# Sheet2.net
KiCad netlist of a schematic drawn in Altium Designer
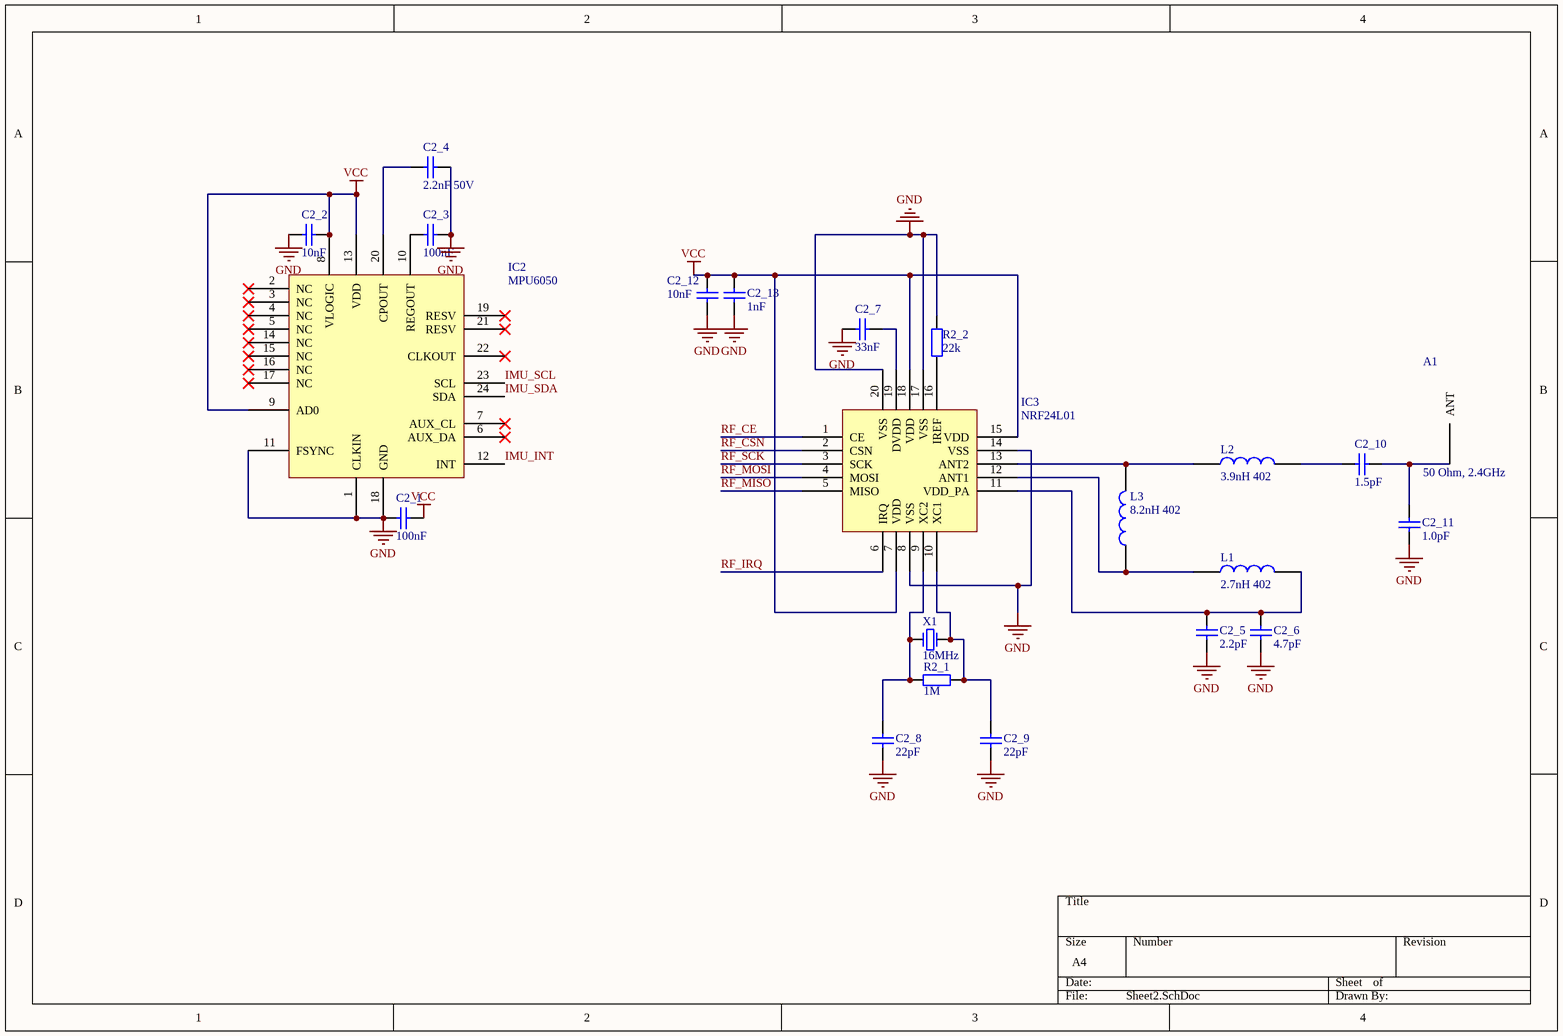
[diagram p0: Sheet2.SchDoc]

(export (version "E")
  (design (tool "Eeschema 10.0.6"))
  (components
    (comp (ref "A1")
      (value "50 Ohm, 2.4GHz")
      (footprint "Antene")
      (libsource (lib "Integrated_Library1") (part "Antenne"))
    )
    (comp (ref "C2_1")
      (value "100nF")
      (footprint "cms805")
      (libsource (lib "Integrated_Library1") (part "Capa"))
    )
    (comp (ref "C2_2")
      (value "10nF")
      (footprint "cms805")
      (libsource (lib "Integrated_Library1") (part "Capa"))
    )
    (comp (ref "C2_3")
      (value "100nF")
      (footprint "cms805")
      (libsource (lib "Integrated_Library1") (part "Capa"))
    )
    (comp (ref "C2_4")
      (value "2.2nF 50V")
      (footprint "cms805")
      (libsource (lib "Integrated_Library1") (part "Capa"))
    )
    (comp (ref "C2_5")
      (value "2.2pF")
      (footprint "cms805")
      (libsource (lib "Integrated_Library1") (part "Capa"))
    )
    (comp (ref "C2_6")
      (value "4.7pF")
      (footprint "cms805")
      (libsource (lib "Integrated_Library1") (part "Capa"))
    )
    (comp (ref "C2_7")
      (value "33nF")
      (footprint "cms805")
      (libsource (lib "Integrated_Library1") (part "Capa"))
    )
    (comp (ref "C2_8")
      (value "22pF")
      (footprint "cms805")
      (libsource (lib "Integrated_Library1") (part "Capa"))
    )
    (comp (ref "C2_9")
      (value "22pF")
      (footprint "cms805")
      (libsource (lib "Integrated_Library1") (part "Capa"))
    )
    (comp (ref "C2_10")
      (value "1.5pF")
      (footprint "cms805")
      (libsource (lib "Integrated_Library1") (part "Capa"))
    )
    (comp (ref "C2_11")
      (value "1.0pF")
      (footprint "cms805")
      (libsource (lib "Integrated_Library1") (part "Capa"))
    )
    (comp (ref "C2_12")
      (value "10nF")
      (footprint "cms805")
      (libsource (lib "Integrated_Library1") (part "Capa"))
    )
    (comp (ref "C2_13")
      (value "1nF")
      (footprint "cms805")
      (libsource (lib "Integrated_Library1") (part "Capa"))
    )
    (comp (ref "IC2")
      (value "MPU6050")
      (footprint "24QFN")
      (libsource (lib "Integrated_Library1") (part "MPU6050"))
    )
    (comp (ref "IC3")
      (value "NRF24L01")
      (footprint "20QFN")
      (libsource (lib "Integrated_Library1") (part "NRF24L01"))
    )
    (comp (ref "L1")
      (value "2.7nH 402")
      (footprint "CMS402")
      (libsource (lib "Integrated_Library1") (part "Inductance"))
    )
    (comp (ref "L2")
      (value "3.9nH 402")
      (footprint "CMS402")
      (libsource (lib "Integrated_Library1") (part "Inductance"))
    )
    (comp (ref "L3")
      (value "8.2nH 402")
      (footprint "CMS402")
      (libsource (lib "Integrated_Library1") (part "Inductance"))
    )
    (comp (ref "R2_1") (value "1M") (footprint "cms805") (libsource (lib "") (part "Resistance_1")))
    (comp (ref "R2_2")
      (value "22k")
      (footprint "cms805")
      (libsource (lib "Integrated_Library1") (part "Resistance"))
    )
    (comp (ref "X1")
      (value "16MHz")
      (footprint "Quartz")
      (libsource (lib "Integrated_Library1") (part "Quartz"))
    )
  )
  (nets
    (net (code "1") (name "/IMU_INT") (class "Default")
      (node (ref "IC2") (pin "12") (pinfunction "INT_12") (pintype "passive"))
    )
    (net (code "2") (name "/IMU_SCL") (class "Default")
      (node (ref "IC2") (pin "23") (pinfunction "SCL_23") (pintype "passive"))
    )
    (net (code "3") (name "/IMU_SDA") (class "Default")
      (node (ref "IC2") (pin "24") (pinfunction "SDA_24") (pintype "passive"))
    )
    (net (code "4") (name "/RF_CE") (class "Default")
      (node (ref "IC3") (pin "1") (pinfunction "CE_1") (pintype "passive"))
    )
    (net (code "5") (name "/RF_CSN") (class "Default")
      (node (ref "IC3") (pin "2") (pinfunction "CSN_2") (pintype "passive"))
    )
    (net (code "6") (name "/RF_IRQ") (class "Default")
      (node (ref "IC3") (pin "6") (pinfunction "IRQ_6") (pintype "passive"))
    )
    (net (code "7") (name "/RF_MISO") (class "Default")
      (node (ref "IC3") (pin "5") (pinfunction "MISO_5") (pintype "passive"))
    )
    (net (code "8") (name "/RF_MOSI") (class "Default")
      (node (ref "IC3") (pin "4") (pinfunction "MOSI_4") (pintype "passive"))
    )
    (net (code "9") (name "/RF_SCK") (class "Default")
      (node (ref "IC3") (pin "3") (pinfunction "SCK_3") (pintype "passive"))
    )
    (net (code "10") (name "GND") (class "Default")
      (node (ref "C2_1") (pin "1") (pinfunction "1_1") (pintype "passive"))
      (node (ref "C2_11") (pin "2") (pinfunction "2_2") (pintype "passive"))
      (node (ref "C2_12") (pin "2") (pinfunction "2_2") (pintype "passive"))
      (node (ref "C2_13") (pin "2") (pinfunction "2_2") (pintype "passive"))
      (node (ref "C2_2") (pin "2") (pinfunction "2_2") (pintype "passive"))
      (node (ref "C2_3") (pin "2") (pinfunction "2_2") (pintype "passive"))
      (node (ref "C2_4") (pin "1") (pinfunction "1_1") (pintype "passive"))
      (node (ref "C2_5") (pin "2") (pinfunction "2_2") (pintype "passive"))
      (node (ref "C2_6") (pin "2") (pinfunction "2_2") (pintype "passive"))
      (node (ref "C2_7") (pin "2") (pinfunction "2_2") (pintype "passive"))
      (node (ref "C2_8") (pin "1") (pinfunction "1_1") (pintype "passive"))
      (node (ref "C2_9") (pin "1") (pinfunction "1_1") (pintype "passive"))
      (node (ref "IC2") (pin "1") (pinfunction "CLKIN_1") (pintype "passive"))
      (node (ref "IC2") (pin "11") (pinfunction "FSYNC_11") (pintype "passive"))
      (node (ref "IC2") (pin "18") (pinfunction "GND_18") (pintype "passive"))
      (node (ref "IC3") (pin "14") (pinfunction "VSS_14") (pintype "passive"))
      (node (ref "IC3") (pin "17") (pinfunction "VSS_17") (pintype "passive"))
      (node (ref "IC3") (pin "20") (pinfunction "VSS_20") (pintype "passive"))
      (node (ref "IC3") (pin "8") (pinfunction "VSS_8") (pintype "passive"))
      (node (ref "R2_2") (pin "2") (pinfunction "2_2") (pintype "passive"))
    )
    (net (code "11") (name "Net-(A1-ANT)") (class "Default")
      (node (ref "A1") (pin "1") (pinfunction "ANT_1") (pintype "passive"))
      (node (ref "C2_10") (pin "1") (pinfunction "1_1") (pintype "passive"))
      (node (ref "C2_11") (pin "1") (pinfunction "1_1") (pintype "passive"))
    )
    (net (code "12") (name "Net-(C2_10-Pad2)") (class "Default")
      (node (ref "C2_10") (pin "2") (pinfunction "2_2") (pintype "passive"))
      (node (ref "L2") (pin "2") (pinfunction "2_2") (pintype "passive"))
    )
    (net (code "13") (name "Net-(IC2-CPOUT)") (class "Default")
      (node (ref "C2_4") (pin "2") (pinfunction "2_2") (pintype "passive"))
      (node (ref "IC2") (pin "20") (pinfunction "CPOUT_20") (pintype "passive"))
    )
    (net (code "14") (name "Net-(IC2-REGOUT)") (class "Default")
      (node (ref "C2_3") (pin "1") (pinfunction "1_1") (pintype "passive"))
      (node (ref "IC2") (pin "10") (pinfunction "REGOUT_10") (pintype "passive"))
    )
    (net (code "15") (name "Net-(IC3-ANT1)") (class "Default")
      (node (ref "IC3") (pin "12") (pinfunction "ANT1_12") (pintype "passive"))
      (node (ref "L1") (pin "1") (pinfunction "1_1") (pintype "passive"))
      (node (ref "L3") (pin "1") (pinfunction "1_1") (pintype "passive"))
    )
    (net (code "16") (name "Net-(IC3-ANT2)") (class "Default")
      (node (ref "IC3") (pin "13") (pinfunction "ANT2_13") (pintype "passive"))
      (node (ref "L2") (pin "1") (pinfunction "1_1") (pintype "passive"))
      (node (ref "L3") (pin "2") (pinfunction "2_2") (pintype "passive"))
    )
    (net (code "17") (name "Net-(IC3-DVDD)") (class "Default")
      (node (ref "C2_7") (pin "1") (pinfunction "1_1") (pintype "passive"))
      (node (ref "IC3") (pin "19") (pinfunction "DVDD_19") (pintype "passive"))
    )
    (net (code "18") (name "Net-(IC3-IREF)") (class "Default")
      (node (ref "IC3") (pin "16") (pinfunction "IREF_16") (pintype "passive"))
      (node (ref "R2_2") (pin "1") (pinfunction "1_1") (pintype "passive"))
    )
    (net (code "19") (name "Net-(IC3-VDD_PA)") (class "Default")
      (node (ref "C2_5") (pin "1") (pinfunction "1_1") (pintype "passive"))
      (node (ref "C2_6") (pin "1") (pinfunction "1_1") (pintype "passive"))
      (node (ref "IC3") (pin "11") (pinfunction "VDD_PA_11") (pintype "passive"))
      (node (ref "L1") (pin "2") (pinfunction "2_2") (pintype "passive"))
    )
    (net (code "20") (name "Net-(IC3-XC1)") (class "Default")
      (node (ref "C2_9") (pin "2") (pinfunction "2_2") (pintype "passive"))
      (node (ref "IC3") (pin "10") (pinfunction "XC1_10") (pintype "passive"))
      (node (ref "R2_1") (pin "2") (pinfunction "2_2") (pintype "passive"))
      (node (ref "X1") (pin "2") (pinfunction "2_2") (pintype "passive"))
    )
    (net (code "21") (name "Net-(IC3-XC2)") (class "Default")
      (node (ref "C2_8") (pin "2") (pinfunction "2_2") (pintype "passive"))
      (node (ref "IC3") (pin "9") (pinfunction "XC2_9") (pintype "passive"))
      (node (ref "R2_1") (pin "1") (pinfunction "1_1") (pintype "passive"))
      (node (ref "X1") (pin "1") (pinfunction "1_1") (pintype "passive"))
    )
    (net (code "22") (name "VCC") (class "Default")
      (node (ref "C2_1") (pin "2") (pinfunction "2_2") (pintype "passive"))
      (node (ref "C2_12") (pin "1") (pinfunction "1_1") (pintype "passive"))
      (node (ref "C2_13") (pin "1") (pinfunction "1_1") (pintype "passive"))
      (node (ref "C2_2") (pin "1") (pinfunction "1_1") (pintype "passive"))
      (node (ref "IC2") (pin "13") (pinfunction "VDD_13") (pintype "passive"))
      (node (ref "IC2") (pin "8") (pinfunction "VLOGIC_8") (pintype "passive"))
      (node (ref "IC2") (pin "9") (pinfunction "AD0_9") (pintype "passive"))
      (node (ref "IC3") (pin "15") (pinfunction "VDD_15") (pintype "passive"))
      (node (ref "IC3") (pin "18") (pinfunction "VDD_18") (pintype "passive"))
      (node (ref "IC3") (pin "7") (pinfunction "VDD_7") (pintype "passive"))
    )
    (net (code "23") (name "unconnected-(IC2-AUX_CL-Pad7)") (class "Default")
      (node (ref "IC2") (pin "7") (pinfunction "AUX_CL_7") (pintype "passive+no_connect"))
    )
    (net (code "24") (name "unconnected-(IC2-AUX_DA-Pad6)") (class "Default")
      (node (ref "IC2") (pin "6") (pinfunction "AUX_DA_6") (pintype "passive+no_connect"))
    )
    (net (code "25") (name "unconnected-(IC2-CLKOUT-Pad22)") (class "Default")
      (node (ref "IC2") (pin "22") (pinfunction "CLKOUT_22") (pintype "passive+no_connect"))
    )
    (net (code "26") (name "unconnected-(IC2-NC-Pad2)") (class "Default")
      (node (ref "IC2") (pin "2") (pinfunction "NC_2") (pintype "passive+no_connect"))
    )
    (net (code "27") (name "unconnected-(IC2-NC-Pad3)") (class "Default")
      (node (ref "IC2") (pin "3") (pinfunction "NC_3") (pintype "passive+no_connect"))
    )
    (net (code "28") (name "unconnected-(IC2-NC-Pad4)") (class "Default")
      (node (ref "IC2") (pin "4") (pinfunction "NC_4") (pintype "passive+no_connect"))
    )
    (net (code "29") (name "unconnected-(IC2-NC-Pad5)") (class "Default")
      (node (ref "IC2") (pin "5") (pinfunction "NC_5") (pintype "passive+no_connect"))
    )
    (net (code "30") (name "unconnected-(IC2-NC-Pad14)") (class "Default")
      (node (ref "IC2") (pin "14") (pinfunction "NC_14") (pintype "passive+no_connect"))
    )
    (net (code "31") (name "unconnected-(IC2-NC-Pad15)") (class "Default")
      (node (ref "IC2") (pin "15") (pinfunction "NC_15") (pintype "passive+no_connect"))
    )
    (net (code "32") (name "unconnected-(IC2-NC-Pad16)") (class "Default")
      (node (ref "IC2") (pin "16") (pinfunction "NC_16") (pintype "passive+no_connect"))
    )
    (net (code "33") (name "unconnected-(IC2-NC-Pad17)") (class "Default")
      (node (ref "IC2") (pin "17") (pinfunction "NC_17") (pintype "passive+no_connect"))
    )
    (net (code "34") (name "unconnected-(IC2-RESV-Pad19)") (class "Default")
      (node (ref "IC2") (pin "19") (pinfunction "RESV_19") (pintype "passive+no_connect"))
    )
    (net (code "35") (name "unconnected-(IC2-RESV-Pad21)") (class "Default")
      (node (ref "IC2") (pin "21") (pinfunction "RESV_21") (pintype "passive+no_connect"))
    )
  )
)
